# power.net
KiCad netlist of a schematic drawn in Altium Designer
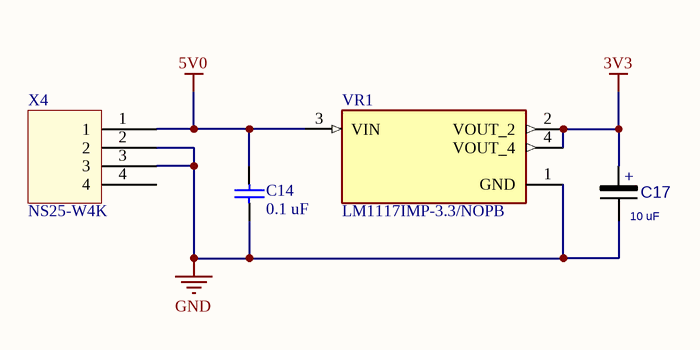
[diagram p0: power.SchDoc]

(export (version "E")
  (design (tool "Eeschema 10.0.6"))
  (components
    (comp (ref "C14")
      (value "0.1 uF")
      (footprint "0805 chip cap")
      (description "Capacitor")
      (libsource (lib "Schlib") (part "Cap"))
    )
    (comp (ref "C17")
      (value "10 uF")
      (footprint "CAP CASE-A")
      (libsource (lib "Schlib") (part "CAP POL CASE A"))
    )
    (comp (ref "VR1")
      (value "LM1117IMP-3.3/NOPB")
      (footprint "VREG_LM1117IMP-3.3/NOPB")
      (description "800-mA 15-V linear voltage regulator 4-SOT-223 0 to 125")
      (libsource (lib "Schlib") (part "LM1117IMP-3.3/NOPB"))
    )
    (comp (ref "X4") (value "NS25-W4K") (footprint "NS25-W4K") (libsource (lib "Schlib") (part "NS25-W4K")))
  )
  (nets
    (net (code "1") (name "3V3") (class "Default")
      (node (ref "C17") (pin "1") (pinfunction "1_1") (pintype "passive"))
      (node (ref "VR1") (pin "2") (pinfunction "VOUT_2_2") (pintype "output"))
      (node (ref "VR1") (pin "4") (pinfunction "VOUT_4_4") (pintype "output"))
    )
    (net (code "2") (name "5V0") (class "Default")
      (node (ref "C14") (pin "2") (pinfunction "2_2") (pintype "passive"))
      (node (ref "VR1") (pin "3") (pinfunction "VIN_3") (pintype "input"))
      (node (ref "X4") (pin "1") (pinfunction "1_1") (pintype "passive"))
    )
    (net (code "3") (name "GND") (class "Default")
      (node (ref "C14") (pin "1") (pinfunction "1_1") (pintype "passive"))
      (node (ref "C17") (pin "2") (pinfunction "2_2") (pintype "passive"))
      (node (ref "VR1") (pin "1") (pinfunction "GND_1") (pintype "power_in"))
      (node (ref "X4") (pin "2") (pinfunction "2_2") (pintype "passive"))
      (node (ref "X4") (pin "3") (pinfunction "3_3") (pintype "passive"))
    )
    (net (code "4") (name "unconnected-(X4-Pad4)") (class "Default")
      (node (ref "X4") (pin "4") (pinfunction "4_4") (pintype "passive"))
    )
  )
)
